# doormonitor.net
KiCad netlist of a schematic drawn in EAGLE
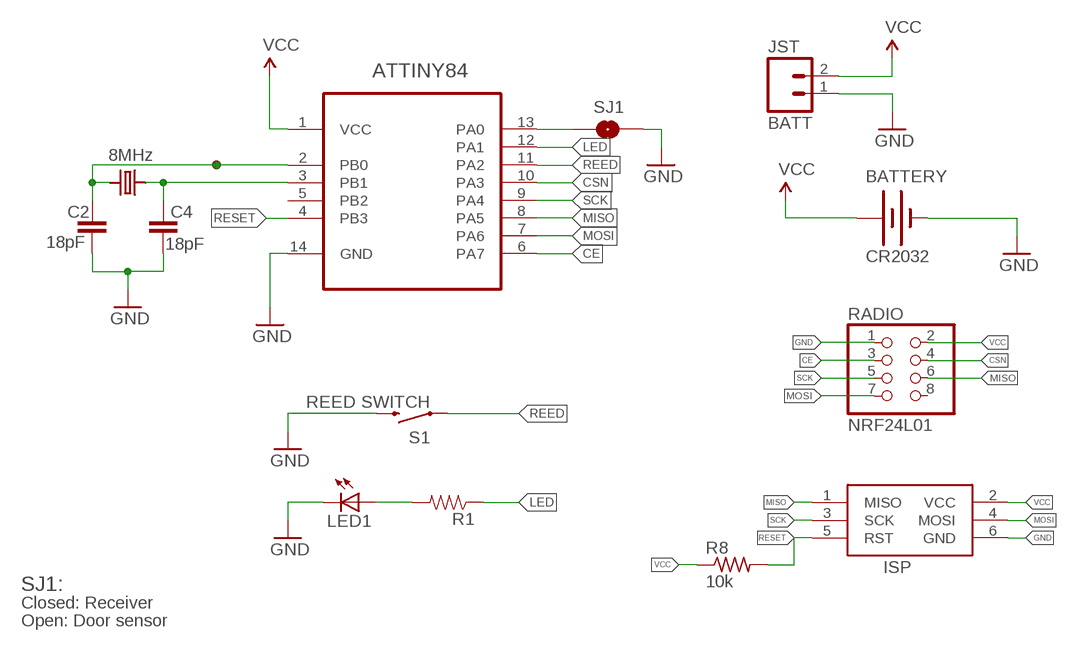
[diagram p0: schematic, sheet 1]

(export (version "E")
  (design (tool "Eeschema 10.0.6"))
  (components
    (comp (ref "ATTINY84")
      (value "ATTINY84-20SSU")
      (footprint "eagle-import:SOIC127P600X175-14N")
      (libsource (lib "eagle-import") (part "ATTINY84-20SSU"))
    )
    (comp (ref "BATTERY")
      (value "CR2032")
      (footprint "eagle-import:BATTCON_20MM_4LEGS_OVERPASTE")
      (libsource (lib "eagle-import") (part "BATTERY20MM_4LEGS_OVERPASTE"))
    )
    (comp (ref "C2")
      (value "18pF")
      (footprint "eagle-import:0805")
      (libsource (lib "eagle-import") (part "CAP0805"))
    )
    (comp (ref "C4")
      (value "18pF")
      (footprint "eagle-import:0805")
      (libsource (lib "eagle-import") (part "CAP0805"))
    )
    (comp (ref "ISP")
      (value "AVRISP-6")
      (footprint "eagle-import:AVRISP")
      (libsource (lib "eagle-import") (part "AVRISP-6"))
    )
    (comp (ref "JST")
      (value "BATT")
      (footprint "eagle-import:JST-2-PTH-VERT")
      (libsource (lib "eagle-import") (part "M02JST-PTH-VERT"))
    )
    (comp (ref "LED1")
      (value "LED5MM")
      (footprint "eagle-import:LED5MM")
      (libsource (lib "eagle-import") (part "LED5MM"))
    )
    (comp (ref "R1")
      (value "RESISTOR0805-RES")
      (footprint "eagle-import:0805")
      (libsource (lib "eagle-import") (part "RESISTOR0805-RES"))
    )
    (comp (ref "R8")
      (value "10k")
      (footprint "eagle-import:R0805")
      (libsource (lib "eagle-import") (part "R-US_R0805"))
    )
    (comp (ref "RADIO")
      (value "NRF24L01")
      (footprint "eagle-import:2X04")
      (libsource (lib "eagle-import") (part "PINHD-2X4"))
    )
    (comp (ref "S1")
      (value "REED SWITCH")
      (footprint "eagle-import:REED_SWITCH_PTH")
      (libsource (lib "eagle-import") (part "SWITCH-MOMENTARY-2PTH_REED"))
    )
    (comp (ref "SJ1")
      (value "Receiver?")
      (footprint "eagle-import:SJ_2S")
      (libsource (lib "eagle-import") (part "SOLDERJUMPERNC"))
    )
    (comp (ref "U$1")
      (value "VIA")
      (footprint "eagle-import:FANCYVIA")
      (libsource (lib "eagle-import") (part "VIA"))
    )
    (comp (ref "Y1")
      (value "8MHz")
      (footprint "eagle-import:NX8045GB")
      (libsource (lib "eagle-import") (part "CRYSTAL"))
    )
  )
  (nets
    (net (code "1") (name "CE") (class "Default")
      (node (ref "ATTINY84") (pin "6") (pinfunction "PA7_6") (pintype "bidirectional"))
      (node (ref "RADIO") (pin "3") (pinfunction "3_3") (pintype "passive"))
    )
    (net (code "2") (name "CSN") (class "Default")
      (node (ref "ATTINY84") (pin "10") (pinfunction "PA3_10") (pintype "bidirectional"))
      (node (ref "RADIO") (pin "4") (pinfunction "4_4") (pintype "passive"))
    )
    (net (code "3") (name "GND") (class "Default")
      (node (ref "ATTINY84") (pin "14") (pinfunction "GND_14") (pintype "passive"))
      (node (ref "BATTERY") (pin "2") (pinfunction "-_2") (pintype "power_in"))
      (node (ref "C2") (pin "2") (pinfunction "2_2") (pintype "passive"))
      (node (ref "C4") (pin "2") (pinfunction "2_2") (pintype "passive"))
      (node (ref "ISP") (pin "6") (pinfunction "GND_6") (pintype "power_in"))
      (node (ref "JST") (pin "1") (pinfunction "1_1") (pintype "passive"))
      (node (ref "LED1") (pin "K") (pinfunction "C_K") (pintype "passive"))
      (node (ref "RADIO") (pin "1") (pinfunction "1_1") (pintype "passive"))
      (node (ref "S1") (pin "P$2") (pinfunction "2_P$2") (pintype "passive"))
      (node (ref "SJ1") (pin "1") (pinfunction "1_1") (pintype "passive"))
    )
    (net (code "4") (name "LED") (class "Default")
      (node (ref "ATTINY84") (pin "12") (pinfunction "PA1_12") (pintype "bidirectional"))
      (node (ref "R1") (pin "1") (pinfunction "1_1") (pintype "passive"))
    )
    (net (code "5") (name "MISO") (class "Default")
      (node (ref "ATTINY84") (pin "8") (pinfunction "PA5_8") (pintype "bidirectional"))
      (node (ref "ISP") (pin "1") (pinfunction "MISO_1") (pintype "input"))
      (node (ref "RADIO") (pin "6") (pinfunction "6_6") (pintype "passive"))
    )
    (net (code "6") (name "MOSI") (class "Default")
      (node (ref "ATTINY84") (pin "7") (pinfunction "PA6_7") (pintype "bidirectional"))
      (node (ref "ISP") (pin "4") (pinfunction "MOSI_4") (pintype "output"))
      (node (ref "RADIO") (pin "7") (pinfunction "7_7") (pintype "passive"))
    )
    (net (code "7") (name "Net-(ATTINY84-PA0)") (class "Default")
      (node (ref "ATTINY84") (pin "13") (pinfunction "PA0_13") (pintype "bidirectional"))
      (node (ref "SJ1") (pin "2") (pinfunction "2_2") (pintype "passive"))
    )
    (net (code "8") (name "Net-(ATTINY84-PB0)") (class "Default")
      (node (ref "ATTINY84") (pin "2") (pinfunction "PB0_2") (pintype "bidirectional"))
      (node (ref "C2") (pin "1") (pinfunction "1_1") (pintype "passive"))
      (node (ref "U$1") (pin "VIA") (pinfunction "1_VIA") (pintype "bidirectional"))
      (node (ref "Y1") (pin "P$2") (pinfunction "2_P$2") (pintype "passive"))
    )
    (net (code "9") (name "Net-(ATTINY84-PB1)") (class "Default")
      (node (ref "ATTINY84") (pin "3") (pinfunction "PB1_3") (pintype "bidirectional"))
      (node (ref "C4") (pin "1") (pinfunction "1_1") (pintype "passive"))
      (node (ref "Y1") (pin "P$1") (pinfunction "1_P$1") (pintype "passive"))
    )
    (net (code "10") (name "Net-(LED1-PadA)") (class "Default")
      (node (ref "LED1") (pin "A") (pinfunction "A_A") (pintype "passive"))
      (node (ref "R1") (pin "2") (pinfunction "2_2") (pintype "passive"))
    )
    (net (code "11") (name "REED") (class "Default")
      (node (ref "ATTINY84") (pin "11") (pinfunction "PA2_11") (pintype "bidirectional"))
      (node (ref "S1") (pin "P$1") (pinfunction "1_P$1") (pintype "passive"))
    )
    (net (code "12") (name "RESET") (class "Default")
      (node (ref "ATTINY84") (pin "4") (pinfunction "PB3_4") (pintype "bidirectional"))
      (node (ref "ISP") (pin "5") (pinfunction "RST_5") (pintype "output"))
      (node (ref "R8") (pin "2") (pinfunction "2_2") (pintype "passive"))
    )
    (net (code "13") (name "SCK") (class "Default")
      (node (ref "ATTINY84") (pin "9") (pinfunction "PA4_9") (pintype "bidirectional"))
      (node (ref "ISP") (pin "3") (pinfunction "SCK_3") (pintype "output"))
      (node (ref "RADIO") (pin "5") (pinfunction "5_5") (pintype "passive"))
    )
    (net (code "14") (name "VCC") (class "Default")
      (node (ref "ATTINY84") (pin "1") (pinfunction "VCC_1") (pintype "power_in"))
      (node (ref "BATTERY") (pin "1") (pinfunction "+_1") (pintype "power_in"))
      (node (ref "ISP") (pin "2") (pinfunction "VCC_2") (pintype "power_in"))
      (node (ref "JST") (pin "2") (pinfunction "2_2") (pintype "passive"))
      (node (ref "R8") (pin "1") (pinfunction "1_1") (pintype "passive"))
      (node (ref "RADIO") (pin "2") (pinfunction "2_2") (pintype "passive"))
    )
    (net (code "15") (name "unconnected-(ATTINY84-PB2-Pad5)") (class "Default")
      (node (ref "ATTINY84") (pin "5") (pinfunction "PB2_5") (pintype "bidirectional"))
    )
    (net (code "16") (name "unconnected-(RADIO-Pad8)") (class "Default")
      (node (ref "RADIO") (pin "8") (pinfunction "8_8") (pintype "passive"))
    )
  )
)
